# SuperJacobv5.net
KiCad netlist of a schematic drawn in EAGLE
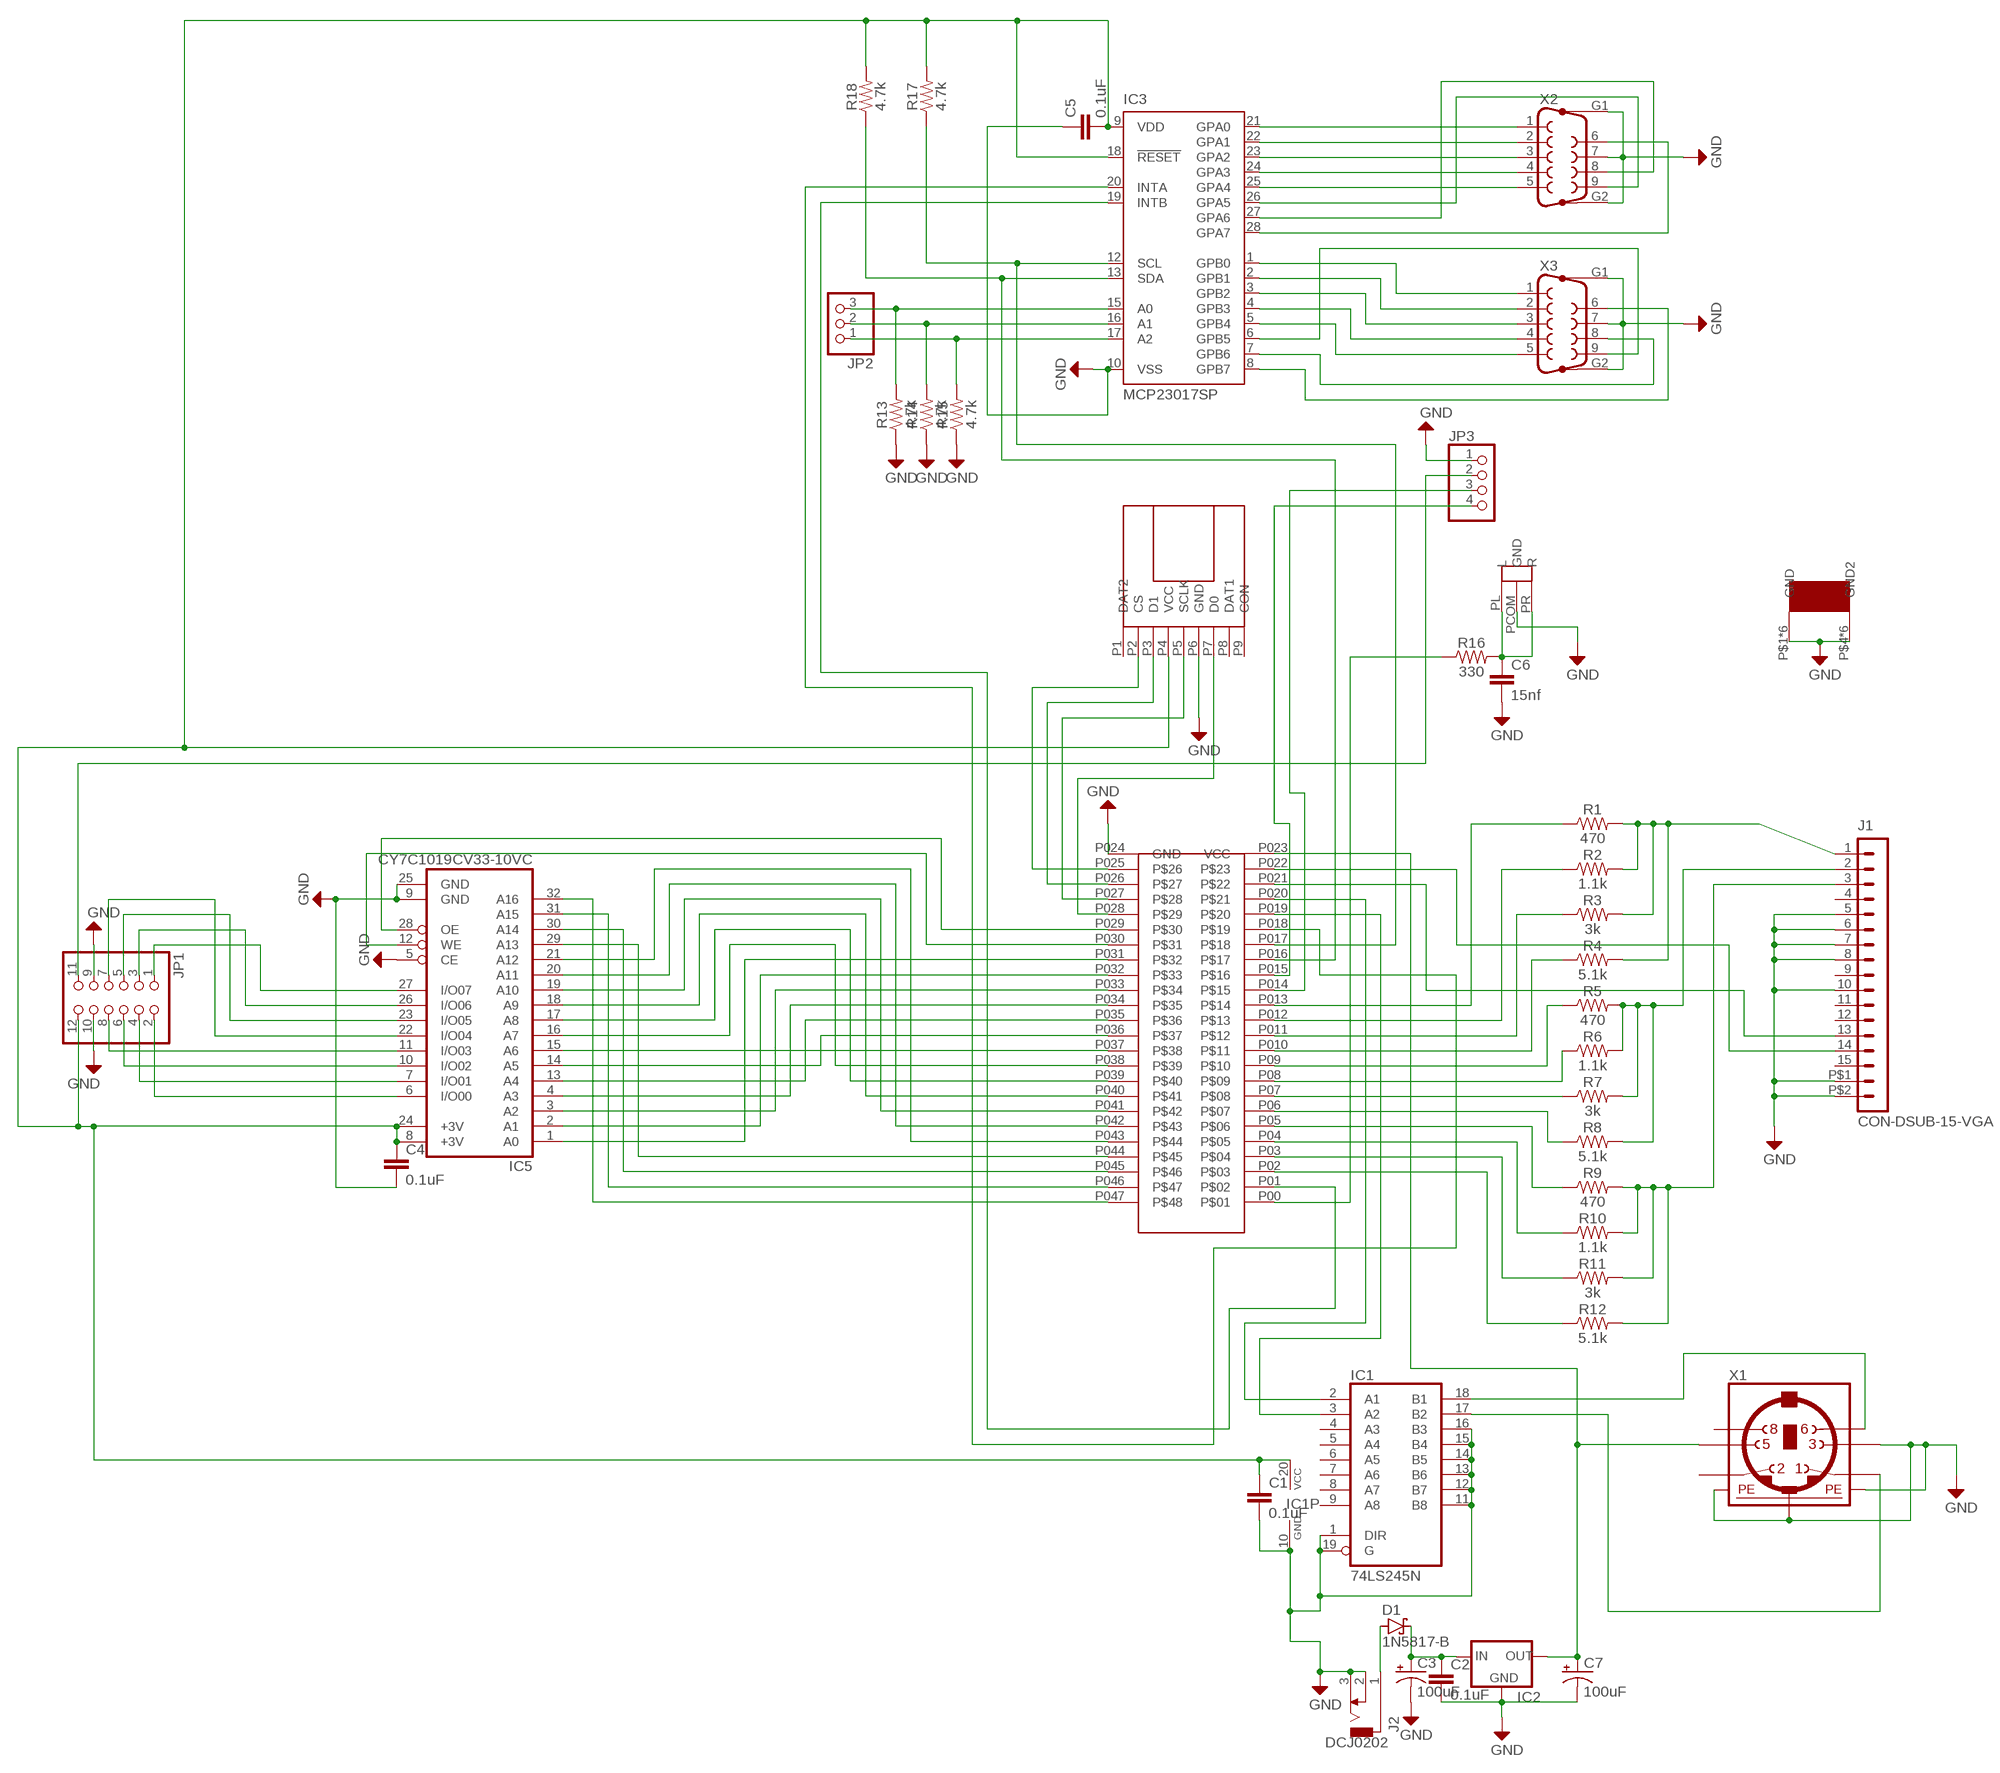
[diagram p0: schematic, sheet 1]

(export (version "E")
  (design (tool "Eeschema 10.0.6"))
  (components
    (comp (ref "C1")
      (value "0.1uF")
      (footprint "eagle-import:CAP-PTH-SMALL-KIT")
      (libsource (lib "eagle-import") (part "0.1UF-KIT-EZ-50V-20%"))
    )
    (comp (ref "C2")
      (value "0.1uF")
      (footprint "eagle-import:CAP-PTH-SMALL-KIT")
      (libsource (lib "eagle-import") (part "0.1UF-KIT-EZ-50V-20%"))
    )
    (comp (ref "C3")
      (value "100uF")
      (footprint "eagle-import:CPOL-RADIAL-2.5MM-5MM")
      (libsource (lib "eagle-import") (part "10UF-POLAR-RADIAL-2.5MM-25V-20%"))
    )
    (comp (ref "C4")
      (value "0.1uF")
      (footprint "eagle-import:CAP-PTH-SMALL-KIT")
      (libsource (lib "eagle-import") (part "0.1UF-KIT-EZ-50V-20%"))
    )
    (comp (ref "C5")
      (value "0.1uF")
      (footprint "eagle-import:CAP-PTH-SMALL-KIT")
      (libsource (lib "eagle-import") (part "0.1UF-KIT-EZ-50V-20%"))
    )
    (comp (ref "C6")
      (value "15nf")
      (footprint "eagle-import:CAP-PTH-SMALL-KIT")
      (libsource (lib "eagle-import") (part "0.1UF-KIT-EZ-50V-20%"))
    )
    (comp (ref "C7")
      (value "100uF")
      (footprint "eagle-import:CPOL-RADIAL-2.5MM-5MM")
      (libsource (lib "eagle-import") (part "10UF-POLAR-RADIAL-2.5MM-25V-20%"))
    )
    (comp (ref "D1")
      (value "1N5817-B")
      (footprint "eagle-import:DO41-7.6")
      (libsource (lib "eagle-import") (part "1N5817-B"))
    )
    (comp (ref "IC1")
      (value "74LS245N")
      (footprint "eagle-import:DIL20")
      (libsource (lib "eagle-import") (part "74245NLS"))
    )
    (comp (ref "IC2")
      (value "78XXL")
      (footprint "eagle-import:78XXL")
      (libsource (lib "eagle-import") (part "78XXL"))
    )
    (comp (ref "IC3")
      (value "MCP23017SP")
      (footprint "eagle-import:DIL28-3")
      (fields (field (name "MF") "MICROCHIP") (field (name "MPN") "MCP23017-E/SP"))
      (libsource (lib "eagle-import") (part "MCP23017SP"))
    )
    (comp (ref "IC5")
      (value "CY7C1019CV33-10VC")
      (footprint "eagle-import:SOJ32-400")
      (libsource (lib "eagle-import") (part "CY7C1019CV33VC-10"))
    )
    (comp (ref "J1")
      (value "CON-DSUB-15-VGA")
      (footprint "eagle-import:181-015-212-171")
      (libsource (lib "eagle-import") (part "CON-DSUB-15-VGA"))
    )
    (comp (ref "J2")
      (value "DCJ0202")
      (footprint "eagle-import:DCJ0202")
      (libsource (lib "eagle-import") (part "DCJ0202"))
    )
    (comp (ref "JP1")
      (value "PINHD-2X6")
      (footprint "eagle-import:2X06")
      (libsource (lib "eagle-import") (part "PINHD-2X6"))
    )
    (comp (ref "JP2")
      (value "PINHD-1X3")
      (footprint "eagle-import:1X03")
      (libsource (lib "eagle-import") (part "PINHD-1X3"))
    )
    (comp (ref "JP3")
      (value "PINHD-1X4")
      (footprint "eagle-import:1X04")
      (libsource (lib "eagle-import") (part "PINHD-1X4"))
    )
    (comp (ref "R1")
      (value "470")
      (footprint "eagle-import:AXIAL-0.3")
      (libsource (lib "eagle-import") (part "1KOHM-HORIZ-1/4W-1%"))
    )
    (comp (ref "R2")
      (value "1.1k")
      (footprint "eagle-import:AXIAL-0.3")
      (libsource (lib "eagle-import") (part "1KOHM-HORIZ-1/4W-1%"))
    )
    (comp (ref "R3")
      (value "3k")
      (footprint "eagle-import:AXIAL-0.3")
      (libsource (lib "eagle-import") (part "1KOHM-HORIZ-1/4W-1%"))
    )
    (comp (ref "R4")
      (value "5.1k")
      (footprint "eagle-import:AXIAL-0.3")
      (libsource (lib "eagle-import") (part "1KOHM-HORIZ-1/4W-1%"))
    )
    (comp (ref "R5")
      (value "470")
      (footprint "eagle-import:AXIAL-0.3")
      (libsource (lib "eagle-import") (part "1KOHM-HORIZ-1/4W-1%"))
    )
    (comp (ref "R6")
      (value "1.1k")
      (footprint "eagle-import:AXIAL-0.3")
      (libsource (lib "eagle-import") (part "1KOHM-HORIZ-1/4W-1%"))
    )
    (comp (ref "R7")
      (value "3k")
      (footprint "eagle-import:AXIAL-0.3")
      (libsource (lib "eagle-import") (part "1KOHM-HORIZ-1/4W-1%"))
    )
    (comp (ref "R8")
      (value "5.1k")
      (footprint "eagle-import:AXIAL-0.3")
      (libsource (lib "eagle-import") (part "1KOHM-HORIZ-1/4W-1%"))
    )
    (comp (ref "R9")
      (value "470")
      (footprint "eagle-import:AXIAL-0.3")
      (libsource (lib "eagle-import") (part "1KOHM-HORIZ-1/4W-1%"))
    )
    (comp (ref "R10")
      (value "1.1k")
      (footprint "eagle-import:AXIAL-0.3")
      (libsource (lib "eagle-import") (part "1KOHM-HORIZ-1/4W-1%"))
    )
    (comp (ref "R11")
      (value "3k")
      (footprint "eagle-import:AXIAL-0.3")
      (libsource (lib "eagle-import") (part "1KOHM-HORIZ-1/4W-1%"))
    )
    (comp (ref "R12")
      (value "5.1k")
      (footprint "eagle-import:AXIAL-0.3")
      (libsource (lib "eagle-import") (part "1KOHM-HORIZ-1/4W-1%"))
    )
    (comp (ref "R13")
      (value "4.7k")
      (footprint "eagle-import:AXIAL-0.3")
      (libsource (lib "eagle-import") (part "1KOHM-HORIZ-1/4W-1%"))
    )
    (comp (ref "R14")
      (value "4.7k")
      (footprint "eagle-import:AXIAL-0.3")
      (libsource (lib "eagle-import") (part "1KOHM-HORIZ-1/4W-1%"))
    )
    (comp (ref "R15")
      (value "4.7k")
      (footprint "eagle-import:AXIAL-0.3")
      (libsource (lib "eagle-import") (part "1KOHM-HORIZ-1/4W-1%"))
    )
    (comp (ref "R16")
      (value "330")
      (footprint "eagle-import:AXIAL-0.3")
      (libsource (lib "eagle-import") (part "1KOHM-HORIZ-1/4W-1%"))
    )
    (comp (ref "R17")
      (value "4.7k")
      (footprint "eagle-import:AXIAL-0.3")
      (libsource (lib "eagle-import") (part "1KOHM-HORIZ-1/4W-1%"))
    )
    (comp (ref "R18")
      (value "4.7k")
      (footprint "eagle-import:AXIAL-0.3")
      (libsource (lib "eagle-import") (part "1KOHM-HORIZ-1/4W-1%"))
    )
    (comp (ref "U$1")
      (value "CMODA7")
      (footprint "eagle-import:CMODA7")
      (libsource (lib "eagle-import") (part "CMODA7"))
    )
    (comp (ref "U$2")
      (value "OPEN-SMARTTFCARDBREAKOUT")
      (footprint "eagle-import:OPEN-SMARTTFCARDBREAKOUT")
      (libsource (lib "eagle-import") (part "OPEN-SMARTTFCARDBREAKOUT"))
    )
    (comp (ref "U$3")
      (value "AUDIOJACK")
      (footprint "eagle-import:AUDIOJACK")
      (libsource (lib "eagle-import") (part "AUDIOJACK"))
    )
    (comp (ref "U$4")
      (value "7085THERMALPAD")
      (footprint "eagle-import:7805THERMALPAD")
      (libsource (lib "eagle-import") (part "7085THERMALPAD"))
    )
    (comp (ref "X1")
      (value "MINI_DIN_6")
      (footprint "eagle-import:M_DIN6")
      (libsource (lib "eagle-import") (part "MINI_DIN_6"))
    )
    (comp (ref "X2")
      (value "F09HP")
      (footprint "eagle-import:F09HP")
      (libsource (lib "eagle-import") (part "F09HP"))
    )
    (comp (ref "X3")
      (value "F09HP")
      (footprint "eagle-import:F09HP")
      (libsource (lib "eagle-import") (part "F09HP"))
    )
  )
  (nets
    (net (code "1") (name "GND") (class "Default")
      (node (ref "C1") (pin "2") (pinfunction "2_2") (pintype "passive"))
      (node (ref "C2") (pin "2") (pinfunction "2_2") (pintype "passive"))
      (node (ref "C3") (pin "2") (pinfunction "-_2") (pintype "passive"))
      (node (ref "C4") (pin "2") (pinfunction "2_2") (pintype "passive"))
      (node (ref "C5") (pin "1") (pinfunction "1_1") (pintype "passive"))
      (node (ref "C6") (pin "2") (pinfunction "2_2") (pintype "passive"))
      (node (ref "C7") (pin "2") (pinfunction "-_2") (pintype "passive"))
      (node (ref "IC1") (pin "1") (pinfunction "DIR_1") (pintype "input"))
      (node (ref "IC1") (pin "10") (pinfunction "GND_10") (pintype "power_in"))
      (node (ref "IC1") (pin "11") (pinfunction "B8_11") (pintype "bidirectional"))
      (node (ref "IC1") (pin "12") (pinfunction "B7_12") (pintype "bidirectional"))
      (node (ref "IC1") (pin "13") (pinfunction "B6_13") (pintype "bidirectional"))
      (node (ref "IC1") (pin "14") (pinfunction "B5_14") (pintype "bidirectional"))
      (node (ref "IC1") (pin "15") (pinfunction "B4_15") (pintype "bidirectional"))
      (node (ref "IC1") (pin "16") (pinfunction "B3_16") (pintype "bidirectional"))
      (node (ref "IC1") (pin "19") (pinfunction "G_19") (pintype "input"))
      (node (ref "IC2") (pin "GND") (pinfunction "GND_GND") (pintype "input"))
      (node (ref "IC3") (pin "10") (pinfunction "VSS_10") (pintype "power_in"))
      (node (ref "IC5") (pin "25") (pinfunction "GND_25") (pintype "power_in"))
      (node (ref "IC5") (pin "5") (pinfunction "CE_5") (pintype "bidirectional"))
      (node (ref "IC5") (pin "9") (pinfunction "GND_9") (pintype "power_in"))
      (node (ref "J1") (pin "10") (pinfunction "10_10") (pintype "passive"))
      (node (ref "J1") (pin "5") (pinfunction "5_5") (pintype "passive"))
      (node (ref "J1") (pin "6") (pinfunction "6_6") (pintype "passive"))
      (node (ref "J1") (pin "7") (pinfunction "7_7") (pintype "passive"))
      (node (ref "J1") (pin "8") (pinfunction "8_8") (pintype "passive"))
      (node (ref "J1") (pin "P$1") (pinfunction "16_P$1") (pintype "passive"))
      (node (ref "J1") (pin "P$2") (pinfunction "17_P$2") (pintype "passive"))
      (node (ref "J2") (pin "2") (pinfunction "2_2") (pintype "passive"))
      (node (ref "J2") (pin "3") (pinfunction "3_3") (pintype "passive"))
      (node (ref "JP1") (pin "10") (pinfunction "10_10") (pintype "passive"))
      (node (ref "JP1") (pin "9") (pinfunction "9_9") (pintype "passive"))
      (node (ref "JP3") (pin "1") (pinfunction "1_1") (pintype "passive"))
      (node (ref "R13") (pin "P$1") (pinfunction "1_P$1") (pintype "passive"))
      (node (ref "R14") (pin "P$1") (pinfunction "1_P$1") (pintype "passive"))
      (node (ref "R15") (pin "P$1") (pinfunction "1_P$1") (pintype "passive"))
      (node (ref "U$1") (pin "P024") (pinfunction "GND_P024") (pintype "power_in"))
      (node (ref "U$2") (pin "P6") (pinfunction "GND_P6") (pintype "power_in"))
      (node (ref "U$3") (pin "PCOM") (pinfunction "GND_PCOM") (pintype "power_in"))
      (node (ref "U$4") (pin "P$1") (pinfunction "GND_P$1") (pintype "power_in"))
      (node (ref "U$4") (pin "P$10") (pinfunction "GND_P$10") (pintype "power_in"))
      (node (ref "U$4") (pin "P$11") (pinfunction "GND2_P$11") (pintype "power_in"))
      (node (ref "U$4") (pin "P$14") (pinfunction "GND2_P$14") (pintype "power_in"))
      (node (ref "U$4") (pin "P$19") (pinfunction "GND2_P$19") (pintype "power_in"))
      (node (ref "U$4") (pin "P$21") (pinfunction "GND2_P$21") (pintype "power_in"))
      (node (ref "U$4") (pin "P$24") (pinfunction "GND2_P$24") (pintype "power_in"))
      (node (ref "U$4") (pin "P$4") (pinfunction "GND2_P$4") (pintype "power_in"))
      (node (ref "U$4") (pin "P$6") (pinfunction "GND_P$6") (pintype "power_in"))
      (node (ref "U$4") (pin "P$7") (pinfunction "GND_P$7") (pintype "power_in"))
      (node (ref "U$4") (pin "P$8") (pinfunction "GND_P$8") (pintype "power_in"))
      (node (ref "U$4") (pin "P$9") (pinfunction "GND_P$9") (pintype "power_in"))
      (node (ref "X1") (pin "3") (pinfunction "3_3") (pintype "passive"))
      (node (ref "X1") (pin "SH1") (pinfunction "PE1_SH1") (pintype "power_in"))
      (node (ref "X1") (pin "SH2") (pinfunction "PE2_SH2") (pintype "power_in"))
      (node (ref "X1") (pin "SH3") (pinfunction "PE3_SH3") (pintype "power_in"))
      (node (ref "X2") (pin "7") (pinfunction "7_7") (pintype "passive"))
      (node (ref "X2") (pin "G1") (pinfunction "G1_G1") (pintype "passive"))
      (node (ref "X2") (pin "G2") (pinfunction "G2_G2") (pintype "passive"))
      (node (ref "X3") (pin "7") (pinfunction "7_7") (pintype "passive"))
      (node (ref "X3") (pin "G1") (pinfunction "G1_G1") (pintype "passive"))
      (node (ref "X3") (pin "G2") (pinfunction "G2_G2") (pintype "passive"))
    )
    (net (code "2") (name "Net-(C3-+)") (class "Default")
      (node (ref "C2") (pin "1") (pinfunction "1_1") (pintype "passive"))
      (node (ref "C3") (pin "1") (pinfunction "+_1") (pintype "passive"))
      (node (ref "D1") (pin "C") (pinfunction "C_C") (pintype "passive"))
      (node (ref "IC2") (pin "IN") (pinfunction "IN_IN") (pintype "input"))
    )
    (net (code "3") (name "Net-(C7-+)") (class "Default")
      (node (ref "C7") (pin "1") (pinfunction "+_1") (pintype "passive"))
      (node (ref "IC2") (pin "OUT") (pinfunction "OUT_OUT") (pintype "passive"))
      (node (ref "U$1") (pin "P023") (pinfunction "VCC_P023") (pintype "power_in"))
      (node (ref "X1") (pin "5") (pinfunction "5_5") (pintype "passive"))
    )
    (net (code "4") (name "Net-(D1-PadA)") (class "Default")
      (node (ref "D1") (pin "A") (pinfunction "A_A") (pintype "passive"))
      (node (ref "J2") (pin "1") (pinfunction "1_1") (pintype "passive"))
    )
    (net (code "5") (name "Net-(IC1A-A1)") (class "Default")
      (node (ref "IC1") (pin "2") (pinfunction "A1_2") (pintype "bidirectional"))
      (node (ref "U$1") (pin "P020") (pinfunction "P$21_P020") (pintype "bidirectional"))
    )
    (net (code "6") (name "Net-(IC1A-A2)") (class "Default")
      (node (ref "IC1") (pin "3") (pinfunction "A2_3") (pintype "bidirectional"))
      (node (ref "U$1") (pin "P019") (pinfunction "P$20_P019") (pintype "bidirectional"))
    )
    (net (code "7") (name "Net-(IC1A-B1)") (class "Default")
      (node (ref "IC1") (pin "18") (pinfunction "B1_18") (pintype "bidirectional"))
      (node (ref "X1") (pin "6") (pinfunction "6_6") (pintype "passive"))
    )
    (net (code "8") (name "Net-(IC1A-B2)") (class "Default")
      (node (ref "IC1") (pin "17") (pinfunction "B2_17") (pintype "bidirectional"))
      (node (ref "X1") (pin "1") (pinfunction "1_1") (pintype "passive"))
    )
    (net (code "9") (name "Net-(IC1B-VCC)") (class "Default")
      (node (ref "C1") (pin "1") (pinfunction "1_1") (pintype "passive"))
      (node (ref "C4") (pin "1") (pinfunction "1_1") (pintype "passive"))
      (node (ref "C5") (pin "2") (pinfunction "2_2") (pintype "passive"))
      (node (ref "IC1") (pin "20") (pinfunction "VCC_20") (pintype "power_in"))
      (node (ref "IC3") (pin "18") (pinfunction "~{RESET}_18") (pintype "input"))
      (node (ref "IC3") (pin "9") (pinfunction "VDD_9") (pintype "power_in"))
      (node (ref "IC5") (pin "24") (pinfunction "+3V_24") (pintype "power_in"))
      (node (ref "IC5") (pin "8") (pinfunction "+3V_8") (pintype "power_in"))
      (node (ref "JP1") (pin "12") (pinfunction "12_12") (pintype "passive"))
      (node (ref "R17") (pin "P$2") (pinfunction "2_P$2") (pintype "passive"))
      (node (ref "R18") (pin "P$2") (pinfunction "2_P$2") (pintype "passive"))
      (node (ref "U$2") (pin "P4") (pinfunction "VCC_P4") (pintype "power_in"))
    )
    (net (code "10") (name "Net-(IC3-A0)") (class "Default")
      (node (ref "IC3") (pin "15") (pinfunction "A0_15") (pintype "input"))
      (node (ref "JP2") (pin "3") (pinfunction "3_3") (pintype "passive"))
      (node (ref "R13") (pin "P$2") (pinfunction "2_P$2") (pintype "passive"))
    )
    (net (code "11") (name "Net-(IC3-A1)") (class "Default")
      (node (ref "IC3") (pin "16") (pinfunction "A1_16") (pintype "input"))
      (node (ref "JP2") (pin "2") (pinfunction "2_2") (pintype "passive"))
      (node (ref "R14") (pin "P$2") (pinfunction "2_P$2") (pintype "passive"))
    )
    (net (code "12") (name "Net-(IC3-A2)") (class "Default")
      (node (ref "IC3") (pin "17") (pinfunction "A2_17") (pintype "input"))
      (node (ref "JP2") (pin "1") (pinfunction "1_1") (pintype "passive"))
      (node (ref "R15") (pin "P$2") (pinfunction "2_P$2") (pintype "passive"))
    )
    (net (code "13") (name "Net-(IC3-GPA0)") (class "Default")
      (node (ref "IC3") (pin "21") (pinfunction "GPA0_21") (pintype "bidirectional"))
      (node (ref "X2") (pin "1") (pinfunction "1_1") (pintype "passive"))
    )
    (net (code "14") (name "Net-(IC3-GPA1)") (class "Default")
      (node (ref "IC3") (pin "22") (pinfunction "GPA1_22") (pintype "bidirectional"))
      (node (ref "X2") (pin "2") (pinfunction "2_2") (pintype "passive"))
    )
    (net (code "15") (name "Net-(IC3-GPA2)") (class "Default")
      (node (ref "IC3") (pin "23") (pinfunction "GPA2_23") (pintype "bidirectional"))
      (node (ref "X2") (pin "3") (pinfunction "3_3") (pintype "passive"))
    )
    (net (code "16") (name "Net-(IC3-GPA3)") (class "Default")
      (node (ref "IC3") (pin "24") (pinfunction "GPA3_24") (pintype "bidirectional"))
      (node (ref "X2") (pin "4") (pinfunction "4_4") (pintype "passive"))
    )
    (net (code "17") (name "Net-(IC3-GPA4)") (class "Default")
      (node (ref "IC3") (pin "25") (pinfunction "GPA4_25") (pintype "bidirectional"))
      (node (ref "X2") (pin "5") (pinfunction "5_5") (pintype "passive"))
    )
    (net (code "18") (name "Net-(IC3-GPA5)") (class "Default")
      (node (ref "IC3") (pin "26") (pinfunction "GPA5_26") (pintype "bidirectional"))
      (node (ref "X2") (pin "9") (pinfunction "9_9") (pintype "passive"))
    )
    (net (code "19") (name "Net-(IC3-GPA6)") (class "Default")
      (node (ref "IC3") (pin "27") (pinfunction "GPA6_27") (pintype "bidirectional"))
      (node (ref "X2") (pin "8") (pinfunction "8_8") (pintype "passive"))
    )
    (net (code "20") (name "Net-(IC3-GPA7)") (class "Default")
      (node (ref "IC3") (pin "28") (pinfunction "GPA7_28") (pintype "bidirectional"))
      (node (ref "X2") (pin "6") (pinfunction "6_6") (pintype "passive"))
    )
    (net (code "21") (name "Net-(IC3-GPB0)") (class "Default")
      (node (ref "IC3") (pin "1") (pinfunction "GPB0_1") (pintype "bidirectional"))
      (node (ref "X3") (pin "1") (pinfunction "1_1") (pintype "passive"))
    )
    (net (code "22") (name "Net-(IC3-GPB1)") (class "Default")
      (node (ref "IC3") (pin "2") (pinfunction "GPB1_2") (pintype "bidirectional"))
      (node (ref "X3") (pin "2") (pinfunction "2_2") (pintype "passive"))
    )
    (net (code "23") (name "Net-(IC3-GPB2)") (class "Default")
      (node (ref "IC3") (pin "3") (pinfunction "GPB2_3") (pintype "bidirectional"))
      (node (ref "X3") (pin "3") (pinfunction "3_3") (pintype "passive"))
    )
    (net (code "24") (name "Net-(IC3-GPB3)") (class "Default")
      (node (ref "IC3") (pin "4") (pinfunction "GPB3_4") (pintype "bidirectional"))
      (node (ref "X3") (pin "4") (pinfunction "4_4") (pintype "passive"))
    )
    (net (code "25") (name "Net-(IC3-GPB4)") (class "Default")
      (node (ref "IC3") (pin "5") (pinfunction "GPB4_5") (pintype "bidirectional"))
      (node (ref "X3") (pin "5") (pinfunction "5_5") (pintype "passive"))
    )
    (net (code "26") (name "Net-(IC3-GPB5)") (class "Default")
      (node (ref "IC3") (pin "6") (pinfunction "GPB5_6") (pintype "bidirectional"))
      (node (ref "X3") (pin "9") (pinfunction "9_9") (pintype "passive"))
    )
    (net (code "27") (name "Net-(IC3-GPB6)") (class "Default")
      (node (ref "IC3") (pin "7") (pinfunction "GPB6_7") (pintype "bidirectional"))
      (node (ref "X3") (pin "8") (pinfunction "8_8") (pintype "passive"))
    )
    (net (code "28") (name "Net-(IC3-GPB7)") (class "Default")
      (node (ref "IC3") (pin "8") (pinfunction "GPB7_8") (pintype "bidirectional"))
      (node (ref "X3") (pin "6") (pinfunction "6_6") (pintype "passive"))
    )
    (net (code "29") (name "Net-(IC3-INTA)") (class "Default")
      (node (ref "IC3") (pin "20") (pinfunction "INTA_20") (pintype "output"))
      (node (ref "U$1") (pin "P018") (pinfunction "P$19_P018") (pintype "bidirectional"))
    )
    (net (code "30") (name "Net-(IC3-INTB)") (class "Default")
      (node (ref "IC3") (pin "19") (pinfunction "INTB_19") (pintype "output"))
      (node (ref "U$1") (pin "P01") (pinfunction "P$02_P01") (pintype "bidirectional"))
    )
    (net (code "31") (name "Net-(IC3-SCL)") (class "Default")
      (node (ref "IC3") (pin "12") (pinfunction "SCL_12") (pintype "input"))
      (node (ref "R17") (pin "P$1") (pinfunction "1_P$1") (pintype "passive"))
      (node (ref "U$1") (pin "P017") (pinfunction "P$18_P017") (pintype "bidirectional"))
    )
    (net (code "32") (name "Net-(IC3-SDA)") (class "Default")
      (node (ref "IC3") (pin "13") (pinfunction "SDA_13") (pintype "bidirectional"))
      (node (ref "R18") (pin "P$1") (pinfunction "1_P$1") (pintype "passive"))
      (node (ref "U$1") (pin "P016") (pinfunction "P$17_P016") (pintype "bidirectional"))
    )
    (net (code "33") (name "Net-(IC5-A0)") (class "Default")
      (node (ref "IC5") (pin "1") (pinfunction "A0_1") (pintype "input"))
      (node (ref "U$1") (pin "P031") (pinfunction "P$32_P031") (pintype "bidirectional"))
    )
    (net (code "34") (name "Net-(IC5-A1)") (class "Default")
      (node (ref "IC5") (pin "2") (pinfunction "A1_2") (pintype "input"))
      (node (ref "U$1") (pin "P032") (pinfunction "P$33_P032") (pintype "bidirectional"))
    )
    (net (code "35") (name "Net-(IC5-A2)") (class "Default")
      (node (ref "IC5") (pin "3") (pinfunction "A2_3") (pintype "input"))
      (node (ref "U$1") (pin "P033") (pinfunction "P$34_P033") (pintype "bidirectional"))
    )
    (net (code "36") (name "Net-(IC5-A3)") (class "Default")
      (node (ref "IC5") (pin "4") (pinfunction "A3_4") (pintype "input"))
      (node (ref "U$1") (pin "P034") (pinfunction "P$35_P034") (pintype "bidirectional"))
    )
    (net (code "37") (name "Net-(IC5-A4)") (class "Default")
      (node (ref "IC5") (pin "13") (pinfunction "A4_13") (pintype "input"))
      (node (ref "U$1") (pin "P035") (pinfunction "P$36_P035") (pintype "bidirectional"))
    )
    (net (code "38") (name "Net-(IC5-A5)") (class "Default")
      (node (ref "IC5") (pin "14") (pinfunction "A5_14") (pintype "input"))
      (node (ref "U$1") (pin "P036") (pinfunction "P$37_P036") (pintype "bidirectional"))
    )
    (net (code "39") (name "Net-(IC5-A6)") (class "Default")
      (node (ref "IC5") (pin "15") (pinfunction "A6_15") (pintype "input"))
      (node (ref "U$1") (pin "P037") (pinfunction "P$38_P037") (pintype "bidirectional"))
    )
    (net (code "40") (name "Net-(IC5-A7)") (class "Default")
      (node (ref "IC5") (pin "16") (pinfunction "A7_16") (pintype "input"))
      (node (ref "U$1") (pin "P038") (pinfunction "P$39_P038") (pintype "bidirectional"))
    )
    (net (code "41") (name "Net-(IC5-A8)") (class "Default")
      (node (ref "IC5") (pin "17") (pinfunction "A8_17") (pintype "input"))
      (node (ref "U$1") (pin "P039") (pinfunction "P$40_P039") (pintype "bidirectional"))
    )
    (net (code "42") (name "Net-(IC5-A9)") (class "Default")
      (node (ref "IC5") (pin "18") (pinfunction "A9_18") (pintype "input"))
      (node (ref "U$1") (pin "P040") (pinfunction "P$41_P040") (pintype "bidirectional"))
    )
    (net (code "43") (name "Net-(IC5-A10)") (class "Default")
      (node (ref "IC5") (pin "19") (pinfunction "A10_19") (pintype "input"))
      (node (ref "U$1") (pin "P041") (pinfunction "P$42_P041") (pintype "bidirectional"))
    )
    (net (code "44") (name "Net-(IC5-A11)") (class "Default")
      (node (ref "IC5") (pin "20") (pinfunction "A11_20") (pintype "input"))
      (node (ref "U$1") (pin "P042") (pinfunction "P$43_P042") (pintype "bidirectional"))
    )
    (net (code "45") (name "Net-(IC5-A12)") (class "Default")
      (node (ref "IC5") (pin "21") (pinfunction "A12_21") (pintype "input"))
      (node (ref "U$1") (pin "P043") (pinfunction "P$44_P043") (pintype "bidirectional"))
    )
    (net (code "46") (name "Net-(IC5-A13)") (class "Default")
      (node (ref "IC5") (pin "29") (pinfunction "A13_29") (pintype "input"))
      (node (ref "U$1") (pin "P044") (pinfunction "P$45_P044") (pintype "bidirectional"))
    )
    (net (code "47") (name "Net-(IC5-A14)") (class "Default")
      (node (ref "IC5") (pin "30") (pinfunction "A14_30") (pintype "input"))
      (node (ref "U$1") (pin "P045") (pinfunction "P$46_P045") (pintype "bidirectional"))
    )
    (net (code "48") (name "Net-(IC5-A15)") (class "Default")
      (node (ref "IC5") (pin "31") (pinfunction "A15_31") (pintype "input"))
      (node (ref "U$1") (pin "P046") (pinfunction "P$47_P046") (pintype "bidirectional"))
    )
    (net (code "49") (name "Net-(IC5-A16)") (class "Default")
      (node (ref "IC5") (pin "32") (pinfunction "A16_32") (pintype "input"))
      (node (ref "U$1") (pin "P047") (pinfunction "P$48_P047") (pintype "bidirectional"))
    )
    (net (code "50") (name "Net-(IC5-I{slash}O00)") (class "Default")
      (node (ref "IC5") (pin "6") (pinfunction "I/O00_6") (pintype "bidirectional"))
      (node (ref "JP1") (pin "2") (pinfunction "2_2") (pintype "passive"))
    )
    (net (code "51") (name "Net-(IC5-I{slash}O01)") (class "Default")
      (node (ref "IC5") (pin "7") (pinfunction "I/O01_7") (pintype "bidirectional"))
      (node (ref "JP1") (pin "4") (pinfunction "4_4") (pintype "passive"))
    )
    (net (code "52") (name "Net-(IC5-I{slash}O02)") (class "Default")
      (node (ref "IC5") (pin "10") (pinfunction "I/O02_10") (pintype "bidirectional"))
      (node (ref "JP1") (pin "6") (pinfunction "6_6") (pintype "passive"))
    )
    (net (code "53") (name "Net-(IC5-I{slash}O03)") (class "Default")
      (node (ref "IC5") (pin "11") (pinfunction "I/O03_11") (pintype "bidirectional"))
      (node (ref "JP1") (pin "8") (pinfunction "8_8") (pintype "passive"))
    )
    (net (code "54") (name "Net-(IC5-I{slash}O04)") (class "Default")
      (node (ref "IC5") (pin "22") (pinfunction "I/O04_22") (pintype "bidirectional"))
      (node (ref "JP1") (pin "7") (pinfunction "7_7") (pintype "passive"))
    )
    (net (code "55") (name "Net-(IC5-I{slash}O05)") (class "Default")
      (node (ref "IC5") (pin "23") (pinfunction "I/O05_23") (pintype "bidirectional"))
      (node (ref "JP1") (pin "5") (pinfunction "5_5") (pintype "passive"))
    )
    (net (code "56") (name "Net-(IC5-I{slash}O06)") (class "Default")
      (node (ref "IC5") (pin "26") (pinfunction "I/O06_26") (pintype "bidirectional"))
      (node (ref "JP1") (pin "3") (pinfunction "3_3") (pintype "passive"))
    )
    (net (code "57") (name "Net-(IC5-I{slash}O07)") (class "Default")
      (node (ref "IC5") (pin "27") (pinfunction "I/O07_27") (pintype "bidirectional"))
      (node (ref "JP1") (pin "1") (pinfunction "1_1") (pintype "passive"))
    )
    (net (code "58") (name "Net-(IC5-OE)") (class "Default")
      (node (ref "IC5") (pin "28") (pinfunction "OE_28") (pintype "input"))
      (node (ref "U$1") (pin "P029") (pinfunction "P$30_P029") (pintype "bidirectional"))
    )
    (net (code "59") (name "Net-(IC5-WE)") (class "Default")
      (node (ref "IC5") (pin "12") (pinfunction "WE_12") (pintype "input"))
      (node (ref "U$1") (pin "P030") (pinfunction "P$31_P030") (pintype "bidirectional"))
    )
    (net (code "60") (name "Net-(JP1-Pad11)") (class "Default")
      (node (ref "JP1") (pin "11") (pinfunction "11_11") (pintype "passive"))
      (node (ref "JP3") (pin "2") (pinfunction "2_2") (pintype "passive"))
    )
    (net (code "61") (name "Net-(R1-1)") (class "Default")
      (node (ref "R1") (pin "P$1") (pinfunction "1_P$1") (pintype "passive"))
      (node (ref "U$1") (pin "P013") (pinfunction "P$14_P013") (pintype "bidirectional"))
    )
    (net (code "62") (name "Net-(R1-2)") (class "Default")
      (node (ref "J1") (pin "1") (pinfunction "1_1") (pintype "passive"))
      (node (ref "R1") (pin "P$2") (pinfunction "2_P$2") (pintype "passive"))
      (node (ref "R2") (pin "P$2") (pinfunction "2_P$2") (pintype "passive"))
      (node (ref "R3") (pin "P$2") (pinfunction "2_P$2") (pintype "passive"))
      (node (ref "R4") (pin "P$2") (pinfunction "2_P$2") (pintype "passive"))
    )
    (net (code "63") (name "Net-(R2-1)") (class "Default")
      (node (ref "R2") (pin "P$1") (pinfunction "1_P$1") (pintype "passive"))
      (node (ref "U$1") (pin "P012") (pinfunction "P$13_P012") (pintype "bidirectional"))
    )
    (net (code "64") (name "Net-(R3-1)") (class "Default")
      (node (ref "R3") (pin "P$1") (pinfunction "1_P$1") (pintype "passive"))
      (node (ref "U$1") (pin "P011") (pinfunction "P$12_P011") (pintype "bidirectional"))
    )
    (net (code "65") (name "Net-(R4-1)") (class "Default")
      (node (ref "R4") (pin "P$1") (pinfunction "1_P$1") (pintype "passive"))
      (node (ref "U$1") (pin "P010") (pinfunction "P$11_P010") (pintype "bidirectional"))
    )
    (net (code "66") (name "Net-(R5-1)") (class "Default")
      (node (ref "R5") (pin "P$1") (pinfunction "1_P$1") (pintype "passive"))
      (node (ref "U$1") (pin "P09") (pinfunction "P$10_P09") (pintype "bidirectional"))
    )
    (net (code "67") (name "Net-(R5-2)") (class "Default")
      (node (ref "J1") (pin "2") (pinfunction "2_2") (pintype "passive"))
      (node (ref "R5") (pin "P$2") (pinfunction "2_P$2") (pintype "passive"))
      (node (ref "R6") (pin "P$2") (pinfunction "2_P$2") (pintype "passive"))
      (node (ref "R7") (pin "P$2") (pinfunction "2_P$2") (pintype "passive"))
      (node (ref "R8") (pin "P$2") (pinfunction "2_P$2") (pintype "passive"))
    )
    (net (code "68") (name "Net-(R6-1)") (class "Default")
      (node (ref "R6") (pin "P$1") (pinfunction "1_P$1") (pintype "passive"))
      (node (ref "U$1") (pin "P08") (pinfunction "P$09_P08") (pintype "bidirectional"))
    )
    (net (code "69") (name "Net-(R7-1)") (class "Default")
      (node (ref "R7") (pin "P$1") (pinfunction "1_P$1") (pintype "passive"))
      (node (ref "U$1") (pin "P07") (pinfunction "P$08_P07") (pintype "bidirectional"))
    )
    (net (code "70") (name "Net-(R8-1)") (class "Default")
      (node (ref "R8") (pin "P$1") (pinfunction "1_P$1") (pintype "passive"))
      (node (ref "U$1") (pin "P06") (pinfunction "P$07_P06") (pintype "bidirectional"))
    )
    (net (code "71") (name "Net-(R9-1)") (class "Default")
      (node (ref "R9") (pin "P$1") (pinfunction "1_P$1") (pintype "passive"))
      (node (ref "U$1") (pin "P05") (pinfunction "P$06_P05") (pintype "bidirectional"))
    )
    (net (code "72") (name "Net-(R10-1)") (class "Default")
      (node (ref "R10") (pin "P$1") (pinfunction "1_P$1") (pintype "passive"))
      (node (ref "U$1") (pin "P04") (pinfunction "P$05_P04") (pintype "bidirectional"))
    )
    (net (code "73") (name "Net-(R10-2)") (class "Default")
      (node (ref "J1") (pin "3") (pinfunction "3_3") (pintype "passive"))
      (node (ref "R10") (pin "P$2") (pinfunction "2_P$2") (pintype "passive"))
      (node (ref "R11") (pin "P$2") (pinfunction "2_P$2") (pintype "passive"))
      (node (ref "R12") (pin "P$2") (pinfunction "2_P$2") (pintype "passive"))
      (node (ref "R9") (pin "P$2") (pinfunction "2_P$2") (pintype "passive"))
    )
    (net (code "74") (name "Net-(R11-1)") (class "Default")
      (node (ref "R11") (pin "P$1") (pinfunction "1_P$1") (pintype "passive"))
      (node (ref "U$1") (pin "P03") (pinfunction "P$04_P03") (pintype "bidirectional"))
    )
    (net (code "75") (name "Net-(R12-1)") (class "Default")
      (node (ref "R12") (pin "P$1") (pinfunction "1_P$1") (pintype "passive"))
      (node (ref "U$1") (pin "P02") (pinfunction "P$03_P02") (pintype "bidirectional"))
    )
    (net (code "76") (name "Net-(R16-1)") (class "Default")
      (node (ref "R16") (pin "P$1") (pinfunction "1_P$1") (pintype "passive"))
      (node (ref "U$1") (pin "P00") (pinfunction "P$01_P00") (pintype "bidirectional"))
    )
    (net (code "77") (name "Net-(R16-2)") (class "Default")
      (node (ref "C6") (pin "1") (pinfunction "1_1") (pintype "passive"))
      (node (ref "R16") (pin "P$2") (pinfunction "2_P$2") (pintype "passive"))
      (node (ref "U$3") (pin "PL") (pinfunction "L_PL") (pintype "input"))
      (node (ref "U$3") (pin "PR") (pinfunction "R_PR") (pintype "input"))
    )
    (net (code "78") (name "Net-(U$1-P$15)") (class "Default")
      (node (ref "JP3") (pin "3") (pinfunction "3_3") (pintype "passive"))
      (node (ref "U$1") (pin "P014") (pinfunction "P$15_P014") (pintype "bidirectional"))
    )
    (net (code "79") (name "Net-(U$1-P$16)") (class "Default")
      (node (ref "JP3") (pin "4") (pinfunction "4_4") (pintype "passive"))
      (node (ref "U$1") (pin "P015") (pinfunction "P$16_P015") (pintype "bidirectional"))
    )
    (net (code "80") (name "Net-(U$1-P$22)") (class "Default")
      (node (ref "J1") (pin "13") (pinfunction "13_13") (pintype "passive"))
      (node (ref "U$1") (pin "P021") (pinfunction "P$22_P021") (pintype "bidirectional"))
    )
    (net (code "81") (name "Net-(U$1-P$23)") (class "Default")
      (node (ref "J1") (pin "14") (pinfunction "14_14") (pintype "passive"))
      (node (ref "U$1") (pin "P022") (pinfunction "P$23_P022") (pintype "bidirectional"))
    )
    (net (code "82") (name "Net-(U$1-P$26)") (class "Default")
      (node (ref "U$1") (pin "P025") (pinfunction "P$26_P025") (pintype "bidirectional"))
      (node (ref "U$2") (pin "P2") (pinfunction "CS_P2") (pintype "input"))
    )
    (net (code "83") (name "Net-(U$1-P$27)") (class "Default")
      (node (ref "U$1") (pin "P026") (pinfunction "P$27_P026") (pintype "bidirectional"))
      (node (ref "U$2") (pin "P3") (pinfunction "D1_P3") (pintype "input"))
    )
    (net (code "84") (name "Net-(U$1-P$28)") (class "Default")
      (node (ref "U$1") (pin "P027") (pinfunction "P$28_P027") (pintype "bidirectional"))
      (node (ref "U$2") (pin "P5") (pinfunction "SCLK_P5") (pintype "input"))
    )
    (net (code "85") (name "Net-(U$1-P$29)") (class "Default")
      (node (ref "U$1") (pin "P028") (pinfunction "P$29_P028") (pintype "bidirectional"))
      (node (ref "U$2") (pin "P7") (pinfunction "D0_P7") (pintype "bidirectional"))
    )
    (net (code "86") (name "unconnected-(IC1A-A3-Pad4)") (class "Default")
      (node (ref "IC1") (pin "4") (pinfunction "A3_4") (pintype "bidirectional"))
    )
    (net (code "87") (name "unconnected-(IC1A-A4-Pad5)") (class "Default")
      (node (ref "IC1") (pin "5") (pinfunction "A4_5") (pintype "bidirectional"))
    )
    (net (code "88") (name "unconnected-(IC1A-A5-Pad6)") (class "Default")
      (node (ref "IC1") (pin "6") (pinfunction "A5_6") (pintype "bidirectional"))
    )
    (net (code "89") (name "unconnected-(IC1A-A6-Pad7)") (class "Default")
      (node (ref "IC1") (pin "7") (pinfunction "A6_7") (pintype "bidirectional"))
    )
    (net (code "90") (name "unconnected-(IC1A-A7-Pad8)") (class "Default")
      (node (ref "IC1") (pin "8") (pinfunction "A7_8") (pintype "bidirectional"))
    )
    (net (code "91") (name "unconnected-(IC1A-A8-Pad9)") (class "Default")
      (node (ref "IC1") (pin "9") (pinfunction "A8_9") (pintype "bidirectional"))
    )
    (net (code "92") (name "unconnected-(J1-Pad4)") (class "Default")
      (node (ref "J1") (pin "4") (pinfunction "4_4") (pintype "passive"))
    )
    (net (code "93") (name "unconnected-(J1-Pad9)") (class "Default")
      (node (ref "J1") (pin "9") (pinfunction "9_9") (pintype "passive"))
    )
    (net (code "94") (name "unconnected-(J1-Pad11)") (class "Default")
      (node (ref "J1") (pin "11") (pinfunction "11_11") (pintype "passive"))
    )
    (net (code "95") (name "unconnected-(J1-Pad12)") (class "Default")
      (node (ref "J1") (pin "12") (pinfunction "12_12") (pintype "passive"))
    )
    (net (code "96") (name "unconnected-(J1-Pad15)") (class "Default")
      (node (ref "J1") (pin "15") (pinfunction "15_15") (pintype "passive"))
    )
    (net (code "97") (name "unconnected-(U$2-CON-PadP9)") (class "Default")
      (node (ref "U$2") (pin "P9") (pinfunction "CON_P9") (pintype "bidirectional"))
    )
    (net (code "98") (name "unconnected-(U$2-DAT1-PadP8)") (class "Default")
      (node (ref "U$2") (pin "P8") (pinfunction "DAT1_P8") (pintype "bidirectional"))
    )
    (net (code "99") (name "unconnected-(U$2-DAT2-PadP1)") (class "Default")
      (node (ref "U$2") (pin "P1") (pinfunction "DAT2_P1") (pintype "bidirectional"))
    )
    (net (code "100") (name "unconnected-(X1-Pad2)") (class "Default")
      (node (ref "X1") (pin "2") (pinfunction "2_2") (pintype "passive"))
    )
    (net (code "101") (name "unconnected-(X1-Pad8)") (class "Default")
      (node (ref "X1") (pin "8") (pinfunction "8_8") (pintype "passive"))
    )
  )
)
